# Power_Board_Schematic.net
KiCad netlist of a schematic drawn in Altium Designer
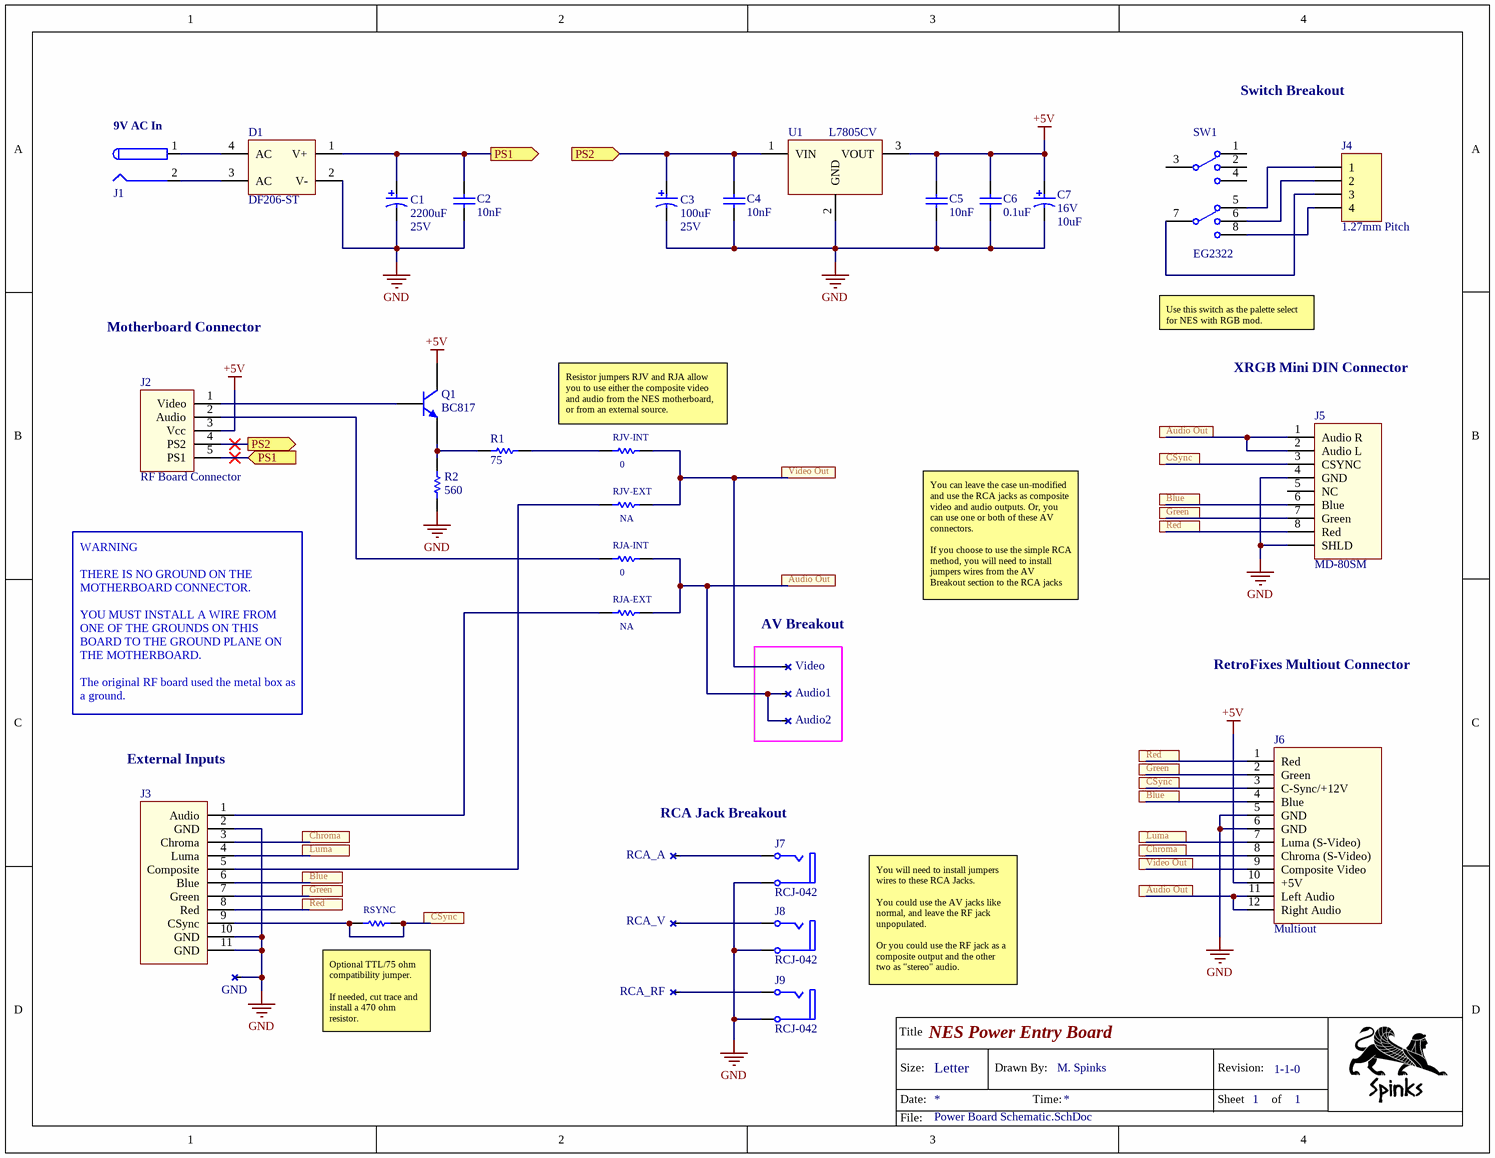
[diagram p0: Power Board Schematic.SchDoc]

(export (version "E")
  (design (tool "Eeschema 10.0.6"))
  (components
    (comp (ref "Audio1")
      (value "Wire Pad")
      (footprint "WIREPAD-09-15")
      (description "Wire Pad, 1 Pin, Through Hole, Vertical")
      (libsource (lib "Connectors") (part "-Wire Pad"))
    )
    (comp (ref "Audio2")
      (value "Wire Pad")
      (footprint "WIREPAD-09-15")
      (description "Wire Pad, 1 Pin, Through Hole, Vertical")
      (libsource (lib "Connectors") (part "-Wire Pad"))
    )
    (comp (ref "C1")
      (value "2200uF")
      (footprint "TH CAP-12.5X25MM-A1K2")
      (description "CAP, ALUM, TH, 12.5x25mm, 2200uF, 25V, 20%, Pitch 5.0mm")
      (fields
        (field (name "VOLTAGE") "25V")
        (field (name "REFERENCEPART") "ECA-1EHG222")
        (field (name "Comment") "Cap Aluminum")
      )
      (libsource (lib "Passive Components") (part "TH-ALUM-8-22-25V (ECA-1EHG222)"))
    )
    (comp (ref "C2")
      (value "10nF")
      (footprint "CAP 0805_N")
      (description "CAP, CER, 0805, 10nF, 50V, X7R, 10%")
      (fields (field (name "VOLTAGE") "50V") (field (name "REFERENCEPART") "VJ0603Y103KXACW1BC"))
      (libsource (lib "Passive Components") (part "0603-X7R-3-10-50V"))
    )
    (comp (ref "C3")
      (value "100uF")
      (footprint "TH CAP-6.3X11MM-A1K2")
      (description "CAP, ALUM, TH, 6.3x11mm, 100uF, 25V, 20%, Pitch 2.5mm")
      (fields
        (field (name "VOLTAGE") "25V")
        (field (name "REFERENCEPART") "ECA-1EM101")
        (field (name "Comment") "Cap Aluminum")
      )
      (libsource (lib "Passive Components") (part "TH-ALUM-7-10-25V (ECA-1EM101)"))
    )
    (comp (ref "C4")
      (value "10nF")
      (footprint "CAP 0805_N")
      (description "CAP, CER, 0805, 10nF, 50V, X7R, 10%")
      (fields (field (name "VOLTAGE") "50V") (field (name "REFERENCEPART") "VJ0603Y103KXACW1BC"))
      (libsource (lib "Passive Components") (part "0603-X7R-3-10-50V"))
    )
    (comp (ref "C5")
      (value "10nF")
      (footprint "CAP 0805_N")
      (description "CAP, CER, 0805, 10nF, 50V, X7R, 10%")
      (fields (field (name "VOLTAGE") "50V") (field (name "REFERENCEPART") "VJ0603Y103KXACW1BC"))
      (libsource (lib "Passive Components") (part "0603-X7R-3-10-50V"))
    )
    (comp (ref "C6")
      (value "0.1uF")
      (footprint "CAP 0805_N")
      (description "CAP, CER, 0805, 0.1uF, 50V, X7R, 10%")
      (fields (field (name "VOLTAGE") "50V") (field (name "REFERENCEPART") "VJ0805Y104KXXCW1BC"))
      (libsource (lib "Passive Components") (part "0805-X7R-4-10-50V"))
    )
    (comp (ref "C7")
      (value "10uF")
      (footprint "CAP EIA-A (3216) A1K2")
      (description "CAP, TANT,  1206, 10uF, 16V, 10%")
      (fields (field (name "VOLTAGE") "16V") (field (name "Comment") "Cap Tantalum"))
      (libsource (lib "Passive Components") (part "1206-TANT-6-10-16V (TAJA106K016RNJ)"))
    )
    (comp (ref "D1")
      (value "DF206-ST")
      (footprint "DFS4")
      (description "Full Wave Diode Bridge")
      (libsource (lib "Semiconductors") (part "Bridge (DF206-ST)"))
    )
    (comp (ref "GND")
      (value "Wire Pad")
      (footprint "WIREPAD-09-15")
      (description "Wire Pad, 1 Pin, Through Hole, Vertical")
      (libsource (lib "Connectors") (part "-Wire Pad"))
    )
    (comp (ref "J1")
      (value "PJ-037A")
      (footprint "PWR-JCK-ALT (PJ-037A/B)")
      (description "2.1mm ID, DC Power Supply Connector, 2 Pin")
      (libsource (lib "Connectors") (part "PWR-JCK (PJ-037A)"))
    )
    (comp (ref "J2")
      (value "RF Board Connector")
      (footprint "RF Board Connector")
      (description "Motherboard Connector to RF/Power Module")
      (libsource (lib "Specialty Components") (part "RF Board Connector"))
    )
    (comp (ref "J3")
      (value "1.27mm Pitch")
      (footprint "RF Board Mod Inputs")
      (description "Video and audio inputs for the RF Board Mod")
      (libsource (lib "Specialty Components") (part "RF Board Mod Input Header"))
    )
    (comp (ref "J4")
      (value "Header 1x4 1.27mm")
      (footprint "HDR1X4-127MM VERT - L")
      (description "Header, 4 Pin, 1.27mm Pitch, Vertical")
      (fields (field (name "LABEL") "1.27mm Pitch"))
      (libsource (lib "Connectors") (part "Header 1x4 - 1.27mm Vert"))
    )
    (comp (ref "J5")
      (value "MD-80SM")
      (footprint "MINI-DIN-8-ALT (MD-80SM)")
      (description "8 Pin Mini DIN Connector, Shielded, Through Hole, Right Angle")
      (libsource (lib "Connectors") (part "Mini-XRGB (MD-80SM)"))
    )
    (comp (ref "J6")
      (value "Multiout")
      (footprint "Multiout-2")
      (description "SNES Multiout Connector")
      (libsource (lib "Specialty Components") (part "Multiout Connector"))
    )
    (comp (ref "J7")
      (value "RCJ-042")
      (footprint "RCA-JCK-1 (RCJ-042-ALT1)")
      (description "RCA Phono Jack, Right Angle")
      (libsource (lib "Connectors") (part "RCA-JCK-1 (RCJ-042)"))
    )
    (comp (ref "J8")
      (value "RCJ-042")
      (footprint "RCA-JCK-1 (RCJ-042-ALT1)")
      (description "RCA Phono Jack, Right Angle")
      (libsource (lib "Connectors") (part "RCA-JCK-1 (RCJ-042)"))
    )
    (comp (ref "J9")
      (value "RCJ-042")
      (footprint "RCA-JCK-1 (RCJ-042-ALT1)")
      (description "RCA Phono Jack, Right Angle")
      (libsource (lib "Connectors") (part "RCA-JCK-1 (RCJ-042)"))
    )
    (comp (ref "Q1")
      (value "BC817")
      (footprint "SOT23-3")
      (description "General Purpose Transistor, NPN, 3-Pin, B1E2C3")
      (fields (field (name "Comment") "Transistor NPN"))
      (libsource (lib "Semiconductors") (part "BC817 NPN"))
    )
    (comp (ref "R1")
      (value "75")
      (footprint "RES 0805_N")
      (description "RES, SMD")
      (fields (field (name "Comment") "Resistor"))
      (libsource (lib "Passive Components") (part "-Resistor"))
    )
    (comp (ref "R2")
      (value "560")
      (footprint "RES 0805_N")
      (description "RES, SMD")
      (fields (field (name "Comment") "Resistor"))
      (libsource (lib "Passive Components") (part "-Resistor"))
    )
    (comp (ref "RCA_A")
      (value "Wire Pad")
      (footprint "WIREPAD-09-15")
      (description "Wire Pad, 1 Pin, Through Hole, Vertical")
      (libsource (lib "Connectors") (part "-Wire Pad"))
    )
    (comp (ref "RCA_RF")
      (value "Wire Pad")
      (footprint "WIREPAD-09-15")
      (description "Wire Pad, 1 Pin, Through Hole, Vertical")
      (libsource (lib "Connectors") (part "-Wire Pad"))
    )
    (comp (ref "RCA_V")
      (value "Wire Pad")
      (footprint "WIREPAD-09-15")
      (description "Wire Pad, 1 Pin, Through Hole, Vertical")
      (libsource (lib "Connectors") (part "-Wire Pad"))
    )
    (comp (ref "RJA-EXT")
      (value "NA")
      (footprint "RES 0805_N")
      (description "RES, SMD")
      (fields (field (name "Comment") "Resistor"))
      (libsource (lib "Passive Components") (part "-Resistor"))
    )
    (comp (ref "RJA-INT")
      (value "0")
      (footprint "RES 0805_N")
      (description "RES, SMD")
      (fields (field (name "Comment") "Resistor"))
      (libsource (lib "Passive Components") (part "-Resistor"))
    )
    (comp (ref "RJV-EXT")
      (value "NA")
      (footprint "RES 0805_N")
      (description "RES, SMD")
      (fields (field (name "Comment") "Resistor"))
      (libsource (lib "Passive Components") (part "-Resistor"))
    )
    (comp (ref "RJV-INT")
      (value "0")
      (footprint "RES 0805_N")
      (description "RES, SMD")
      (fields (field (name "Comment") "Resistor"))
      (libsource (lib "Passive Components") (part "-Resistor"))
    )
    (comp (ref "RSYNC")
      (value "Resistor")
      (footprint "RES 0805_N")
      (description "RES, SMD")
      (libsource (lib "Passive Components") (part "-Resistor"))
    )
    (comp (ref "SW1")
      (value "EG2322")
      (footprint "SW-DP3T (EG2322)")
      (description "Dual Pole, Three Throw")
      (fields (field (name "Comment") "DP3T"))
      (libsource (lib "Electromechanical") (part "SW-DP3T (EG2322)"))
    )
    (comp (ref "U1")
      (value "L7805CV")
      (footprint "TO-220AB")
      (description "Fixed 5V Regulator, 1.5A, Through Hole")
      (libsource (lib "Integrated Circuits") (part "L7805CV"))
    )
    (comp (ref "Video")
      (value "Wire Pad")
      (footprint "WIREPAD-09-15")
      (description "Wire Pad, 1 Pin, Through Hole, Vertical")
      (libsource (lib "Connectors") (part "-Wire Pad"))
    )
  )
  (nets
    (net (code "1") (name "+5V") (class "Default")
      (node (ref "C5") (pin "2") (pinfunction "2_2") (pintype "passive"))
      (node (ref "C6") (pin "2") (pinfunction "2_2") (pintype "passive"))
      (node (ref "C7") (pin "1") (pinfunction "A_1") (pintype "passive"))
      (node (ref "J2") (pin "3") (pinfunction "Vcc_3") (pintype "passive"))
      (node (ref "J6") (pin "10") (pinfunction "+5V_10") (pintype "passive"))
      (node (ref "Q1") (pin "3") (pinfunction "C_3") (pintype "passive"))
      (node (ref "U1") (pin "3") (pinfunction "VOUT_3") (pintype "power_in"))
    )
    (net (code "2") (name "/Audio Out") (class "Default")
      (node (ref "Audio1") (pin "1") (pinfunction "1_1") (pintype "passive"))
      (node (ref "Audio2") (pin "1") (pinfunction "1_1") (pintype "passive"))
      (node (ref "J5") (pin "1") (pinfunction "Audio_R_1") (pintype "passive"))
      (node (ref "J5") (pin "2") (pinfunction "Audio_L_2") (pintype "passive"))
      (node (ref "J6") (pin "11") (pinfunction "Left_Audio_11") (pintype "passive"))
      (node (ref "J6") (pin "12") (pinfunction "Right_Audio_12") (pintype "passive"))
      (node (ref "RJA-EXT") (pin "1") (pinfunction "1_1") (pintype "passive"))
      (node (ref "RJA-INT") (pin "1") (pinfunction "1_1") (pintype "passive"))
    )
    (net (code "3") (name "/Blue") (class "Default")
      (node (ref "J3") (pin "6") (pinfunction "Blue_6") (pintype "passive"))
      (node (ref "J5") (pin "6") (pinfunction "Blue_6") (pintype "passive"))
      (node (ref "J6") (pin "4") (pinfunction "Blue_4") (pintype "passive"))
    )
    (net (code "4") (name "/CSync") (class "Default")
      (node (ref "J3") (pin "9") (pinfunction "CSync_9") (pintype "passive"))
      (node (ref "J5") (pin "3") (pinfunction "CSYNC_3") (pintype "passive"))
      (node (ref "J6") (pin "3") (pinfunction "C-Sync/+12V_3") (pintype "passive"))
      (node (ref "RSYNC") (pin "1") (pinfunction "1_1") (pintype "passive"))
      (node (ref "RSYNC") (pin "2") (pinfunction "2_2") (pintype "passive"))
    )
    (net (code "5") (name "/Chroma") (class "Default")
      (node (ref "J3") (pin "3") (pinfunction "Chroma_3") (pintype "passive"))
      (node (ref "J6") (pin "8") (pinfunction "Chroma_(S-Video)_8") (pintype "passive"))
    )
    (net (code "6") (name "/Green") (class "Default")
      (node (ref "J3") (pin "7") (pinfunction "Green_7") (pintype "passive"))
      (node (ref "J5") (pin "7") (pinfunction "Green_7") (pintype "passive"))
      (node (ref "J6") (pin "2") (pinfunction "Green_2") (pintype "passive"))
    )
    (net (code "7") (name "/Luma") (class "Default")
      (node (ref "J3") (pin "4") (pinfunction "Luma_4") (pintype "passive"))
      (node (ref "J6") (pin "7") (pinfunction "Luma_(S-Video)_7") (pintype "passive"))
    )
    (net (code "8") (name "/PS1") (class "Default")
      (node (ref "C1") (pin "1") (pinfunction "A_1") (pintype "passive"))
      (node (ref "C2") (pin "2") (pinfunction "2_2") (pintype "passive"))
      (node (ref "D1") (pin "1") (pinfunction "V+_1") (pintype "passive"))
      (node (ref "J2") (pin "5") (pinfunction "PS1_5") (pintype "passive"))
    )
    (net (code "9") (name "/PS2") (class "Default")
      (node (ref "C3") (pin "1") (pinfunction "A_1") (pintype "passive"))
      (node (ref "C4") (pin "2") (pinfunction "2_2") (pintype "passive"))
      (node (ref "J2") (pin "4") (pinfunction "PS2_4") (pintype "passive"))
      (node (ref "U1") (pin "1") (pinfunction "VIN_1") (pintype "power_in"))
    )
    (net (code "10") (name "/Red") (class "Default")
      (node (ref "J3") (pin "8") (pinfunction "Red_8") (pintype "passive"))
      (node (ref "J5") (pin "8") (pinfunction "Red_8") (pintype "passive"))
      (node (ref "J6") (pin "1") (pinfunction "Red_1") (pintype "passive"))
    )
    (net (code "11") (name "/Video Out") (class "Default")
      (node (ref "J6") (pin "9") (pinfunction "Composite_Video_9") (pintype "passive"))
      (node (ref "RJV-EXT") (pin "1") (pinfunction "1_1") (pintype "passive"))
      (node (ref "RJV-INT") (pin "1") (pinfunction "1_1") (pintype "passive"))
      (node (ref "Video") (pin "1") (pinfunction "1_1") (pintype "passive"))
    )
    (net (code "12") (name "GND") (class "Default")
      (node (ref "C1") (pin "2") (pinfunction "K_2") (pintype "passive"))
      (node (ref "C2") (pin "1") (pinfunction "1_1") (pintype "passive"))
      (node (ref "C3") (pin "2") (pinfunction "K_2") (pintype "passive"))
      (node (ref "C4") (pin "1") (pinfunction "1_1") (pintype "passive"))
      (node (ref "C5") (pin "1") (pinfunction "1_1") (pintype "passive"))
      (node (ref "C6") (pin "1") (pinfunction "1_1") (pintype "passive"))
      (node (ref "C7") (pin "2") (pinfunction "K_2") (pintype "passive"))
      (node (ref "D1") (pin "2") (pinfunction "V-_2") (pintype "passive"))
      (node (ref "GND") (pin "1") (pinfunction "1_1") (pintype "passive"))
      (node (ref "J3") (pin "10") (pinfunction "GND_10") (pintype "passive"))
      (node (ref "J3") (pin "11") (pinfunction "GND_11") (pintype "passive"))
      (node (ref "J3") (pin "2") (pinfunction "GND_2") (pintype "passive"))
      (node (ref "J5") (pin "4") (pinfunction "GND_4") (pintype "passive"))
      (node (ref "J5") (pin "SHLD") (pinfunction "SHLD_SHLD") (pintype "passive"))
      (node (ref "J6") (pin "5") (pinfunction "GND_5") (pintype "passive"))
      (node (ref "J6") (pin "6") (pinfunction "GND_6") (pintype "passive"))
      (node (ref "J7") (pin "2") (pinfunction "Sleeve_2") (pintype "passive"))
      (node (ref "J8") (pin "2") (pinfunction "Sleeve_2") (pintype "passive"))
      (node (ref "J9") (pin "2") (pinfunction "Sleeve_2") (pintype "passive"))
      (node (ref "R2") (pin "1") (pinfunction "1_1") (pintype "passive"))
      (node (ref "U1") (pin "2") (pinfunction "GND_2") (pintype "passive"))
    )
    (net (code "13") (name "Net-(D1-AC-Pad3)") (class "Default")
      (node (ref "D1") (pin "3") (pinfunction "AC_3") (pintype "passive"))
      (node (ref "J1") (pin "2") (pinfunction "2_2") (pintype "power_in"))
    )
    (net (code "14") (name "Net-(D1-AC-Pad4)") (class "Default")
      (node (ref "D1") (pin "4") (pinfunction "AC_4") (pintype "passive"))
      (node (ref "J1") (pin "1") (pinfunction "1_1") (pintype "power_in"))
    )
    (net (code "15") (name "Net-(J2-Audio)") (class "Default")
      (node (ref "J2") (pin "2") (pinfunction "Audio_2") (pintype "passive"))
      (node (ref "RJA-INT") (pin "2") (pinfunction "2_2") (pintype "passive"))
    )
    (net (code "16") (name "Net-(J2-Video)") (class "Default")
      (node (ref "J2") (pin "1") (pinfunction "Video_1") (pintype "passive"))
      (node (ref "Q1") (pin "1") (pinfunction "B_1") (pintype "passive"))
    )
    (net (code "17") (name "Net-(J3-Audio)") (class "Default")
      (node (ref "J3") (pin "1") (pinfunction "Audio_1") (pintype "passive"))
      (node (ref "RJA-EXT") (pin "2") (pinfunction "2_2") (pintype "passive"))
    )
    (net (code "18") (name "Net-(J3-Composite)") (class "Default")
      (node (ref "J3") (pin "5") (pinfunction "Composite_5") (pintype "passive"))
      (node (ref "RJV-EXT") (pin "2") (pinfunction "2_2") (pintype "passive"))
    )
    (net (code "19") (name "Net-(J4-Pad1)") (class "Default")
      (node (ref "J4") (pin "1") (pinfunction "1_1") (pintype "passive"))
      (node (ref "SW1") (pin "5") (pinfunction "5_5") (pintype "passive"))
    )
    (net (code "20") (name "Net-(J4-Pad2)") (class "Default")
      (node (ref "J4") (pin "2") (pinfunction "2_2") (pintype "passive"))
      (node (ref "SW1") (pin "6") (pinfunction "6_6") (pintype "passive"))
    )
    (net (code "21") (name "Net-(J4-Pad3)") (class "Default")
      (node (ref "J4") (pin "3") (pinfunction "3_3") (pintype "passive"))
      (node (ref "SW1") (pin "7") (pinfunction "7_7") (pintype "passive"))
    )
    (net (code "22") (name "Net-(J4-Pad4)") (class "Default")
      (node (ref "J4") (pin "4") (pinfunction "4_4") (pintype "passive"))
      (node (ref "SW1") (pin "8") (pinfunction "8_8") (pintype "passive"))
    )
    (net (code "23") (name "Net-(J7-Tip)") (class "Default")
      (node (ref "J7") (pin "1") (pinfunction "Tip_1") (pintype "passive"))
      (node (ref "RCA_A") (pin "1") (pinfunction "1_1") (pintype "passive"))
    )
    (net (code "24") (name "Net-(J8-Tip)") (class "Default")
      (node (ref "J8") (pin "1") (pinfunction "Tip_1") (pintype "passive"))
      (node (ref "RCA_V") (pin "1") (pinfunction "1_1") (pintype "passive"))
    )
    (net (code "25") (name "Net-(J9-Tip)") (class "Default")
      (node (ref "J9") (pin "1") (pinfunction "Tip_1") (pintype "passive"))
      (node (ref "RCA_RF") (pin "1") (pinfunction "1_1") (pintype "passive"))
    )
    (net (code "26") (name "Net-(Q1-E)") (class "Default")
      (node (ref "Q1") (pin "2") (pinfunction "E_2") (pintype "passive"))
      (node (ref "R1") (pin "2") (pinfunction "2_2") (pintype "passive"))
      (node (ref "R2") (pin "2") (pinfunction "2_2") (pintype "passive"))
    )
    (net (code "27") (name "Net-(R1-Pad1)") (class "Default")
      (node (ref "R1") (pin "1") (pinfunction "1_1") (pintype "passive"))
      (node (ref "RJV-INT") (pin "2") (pinfunction "2_2") (pintype "passive"))
    )
    (net (code "28") (name "unconnected-(J5-NC-Pad5)") (class "Default")
      (node (ref "J5") (pin "5") (pinfunction "NC_5") (pintype "passive"))
    )
    (net (code "29") (name "unconnected-(SW1-Pad1)") (class "Default")
      (node (ref "SW1") (pin "1") (pinfunction "1_1") (pintype "passive"))
    )
    (net (code "30") (name "unconnected-(SW1-Pad2)") (class "Default")
      (node (ref "SW1") (pin "2") (pinfunction "2_2") (pintype "passive"))
    )
    (net (code "31") (name "unconnected-(SW1-Pad3)") (class "Default")
      (node (ref "SW1") (pin "3") (pinfunction "3_3") (pintype "passive"))
    )
    (net (code "32") (name "unconnected-(SW1-Pad4)") (class "Default")
      (node (ref "SW1") (pin "4") (pinfunction "4_4") (pintype "passive"))
    )
  )
)
